# SCH_Mach_nguyen_ly_thiet_ke.net
KiCad netlist of a schematic drawn in Altium Designer
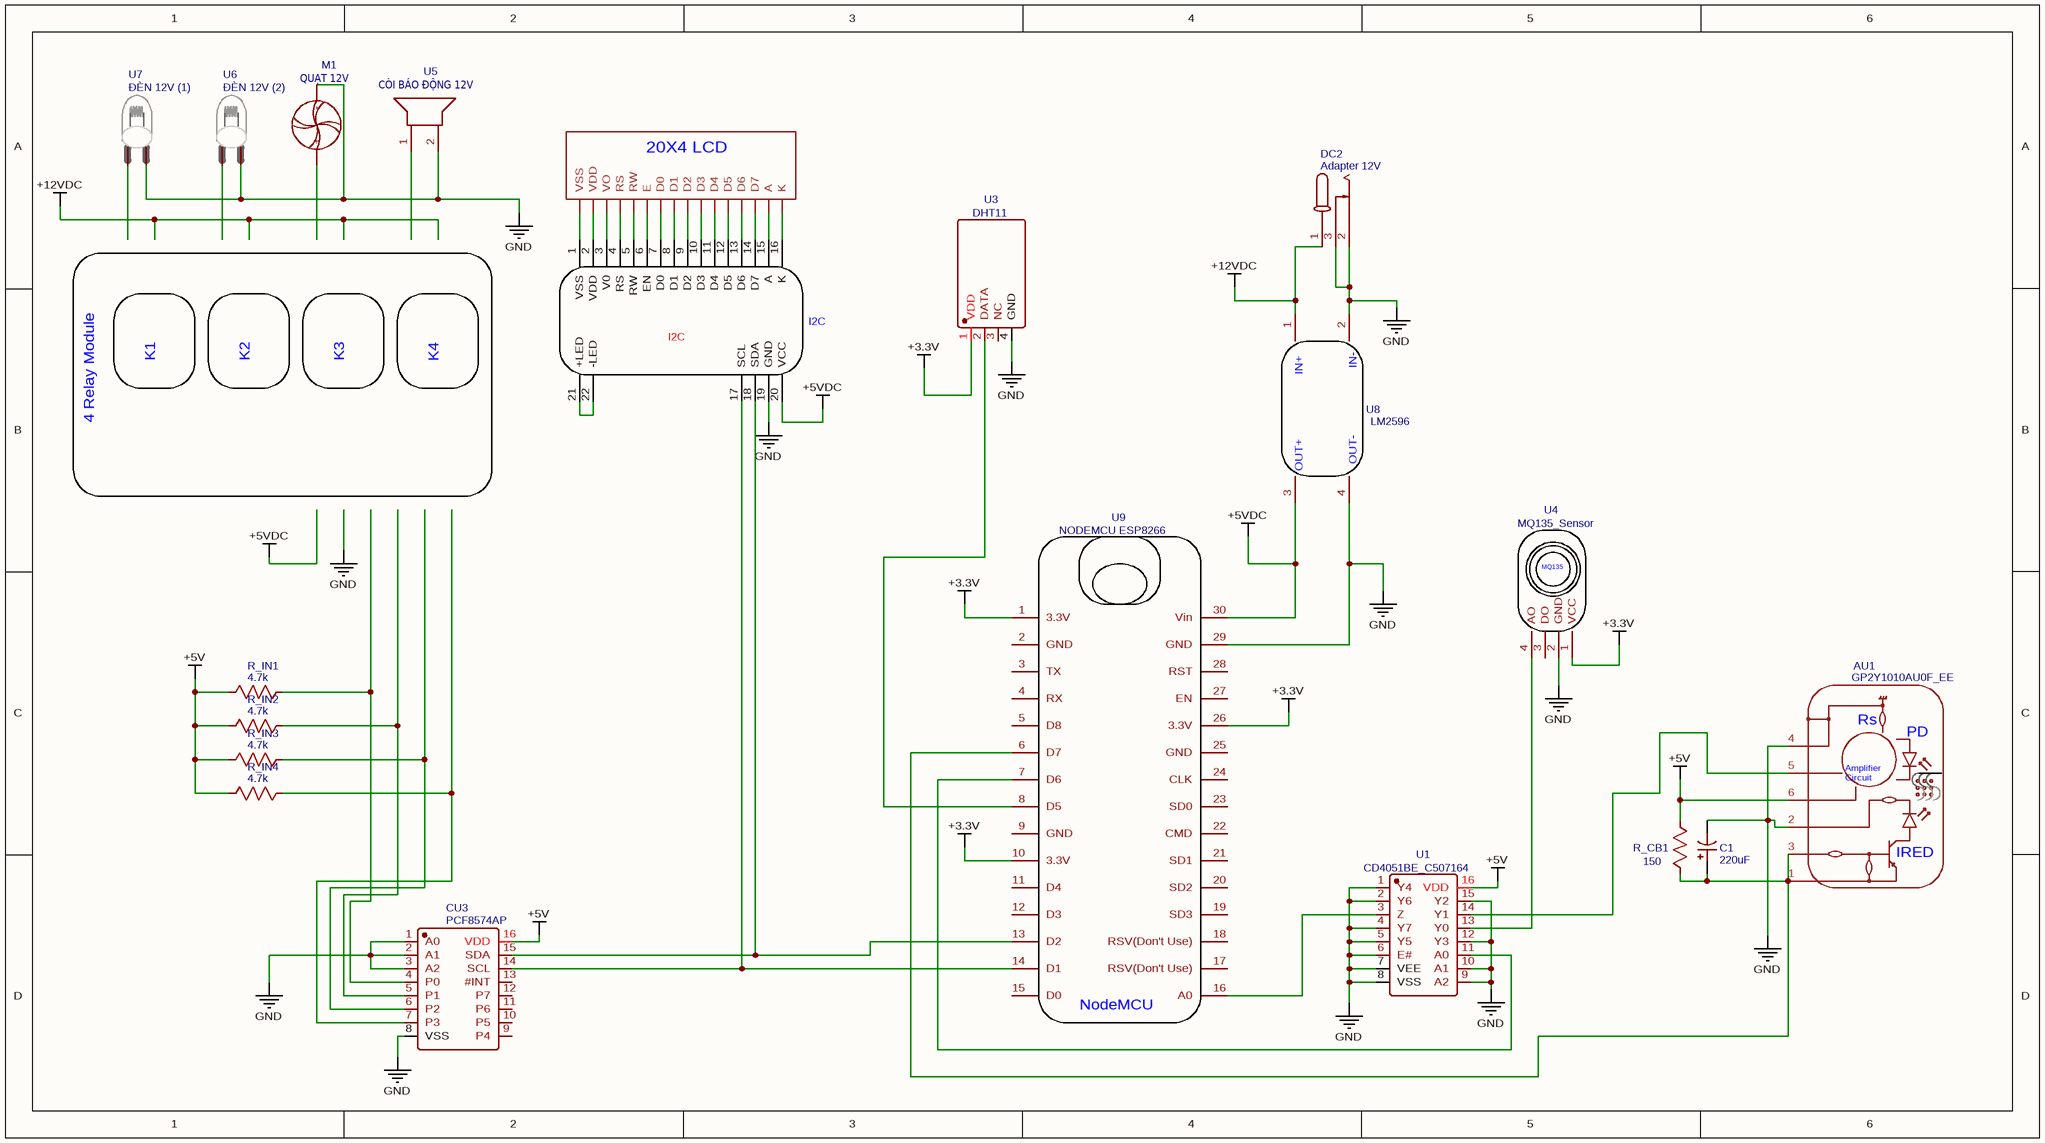
[diagram p0: SCH_Mach_nguyen_ly_thiet_ke.schdoc]

(export (version "E")
  (design (tool "Eeschema 10.0.6"))
  (components
    (comp (ref "AU1")
      (value "GP2Y1010AU0F_EE")
      (footprint "GP2Y1010AU0F")
      (fields (field (name "CONTRIBUTOR") "Ahmed Maher"))
      (libsource (lib "altium-import") (part "root_2_GP2Y1010AU0F_EE_"))
    )
    (comp (ref "C1")
      (value "220uF")
      (footprint "CAP-TH_BD10.0-P5.00-D0.6-FD")
      (fields
        (field (name "MANUFACTURER") "ELNA(伊娜)")
        (field (name "MANUFACTURER PART") "RFO-35V221MH3P#")
        (field (name "CONTRIBUTOR") "lcsc")
      )
      (libsource (lib "altium-import") (part "root_1_220uF_"))
    )
    (comp (ref "CU3")
      (value "PCF8574AP")
      (footprint "DIP-16_L19.2-W6.6-P2.54-LS7.6-BL")
      (fields (field (name "MANUFACTURER") "HGSEMI") (field (name "CONTRIBUTOR") "LCSC"))
      (libsource (lib "altium-import") (part "root_0_PCF8574AP_"))
    )
    (comp (ref "DC2")
      (value "Adapter 12V")
      (footprint "DC-IN-TH_DC005")
      (fields (field (name "MANUFACTURER") "SOFNG") (field (name "MANUFACTURER PART") "DC005-2.0MM"))
      (libsource (lib "altium-import") (part "root_3_Adapter 12V_"))
    )
    (comp (ref "I2C")
      (value "PCF8574AT I2C LCD1602 DRIVER")
      (footprint "PCF8574AT I2C LCD1602 DRIVER 2")
      (fields (field (name "CONTRIBUTOR") "瀬戸口和広"))
      (libsource (lib "altium-import") (part "root_1_PCF8574AT I2C LCD1602 DRIVER_"))
    )
    (comp (ref "M1")
      (value "QUẠT 12V")
      (fields (field (name "CONTRIBUTOR") "KiCAD"))
      (libsource (lib "altium-import") (part "root_2_QUẠT 12V_"))
    )
    (comp (ref "R_CB1")
      (value "150")
      (footprint "R_AXIAL-0.5")
      (fields (field (name "CONTRIBUTOR") "LCEDA_Lib"))
      (libsource (lib "altium-import") (part "root_1_150_"))
    )
    (comp (ref "R_IN1")
      (value "4.7k")
      (footprint "R_AXIAL-0.5")
      (fields (field (name "CONTRIBUTOR") "LCEDA_Lib"))
      (libsource (lib "altium-import") (part "root_0_4.7k_"))
    )
    (comp (ref "R_IN2")
      (value "4.7k")
      (footprint "R_AXIAL-0.5")
      (fields (field (name "CONTRIBUTOR") "LCEDA_Lib"))
      (libsource (lib "altium-import") (part "root_0_4.7k_"))
    )
    (comp (ref "R_IN3")
      (value "4.7k")
      (footprint "R_AXIAL-0.5")
      (fields (field (name "CONTRIBUTOR") "LCEDA_Lib"))
      (libsource (lib "altium-import") (part "root_0_4.7k_"))
    )
    (comp (ref "R_IN4")
      (value "4.7k")
      (footprint "R_AXIAL-0.5")
      (fields (field (name "CONTRIBUTOR") "LCEDA_Lib"))
      (libsource (lib "altium-import") (part "root_0_4.7k_"))
    )
    (comp (ref "TUNNU2")
      (value "LCD-16X28X2-KIT")
      (footprint "LCD-8X2-KIT")
      (fields (field (name "CONTRIBUTOR") "SparkFun"))
      (libsource (lib "altium-import") (part "root_3_LCD-16X28X2-KIT_"))
    )
    (comp (ref "U1")
      (value "CD4051BE_C507164")
      (footprint "DIP-16_L20.0-W6.4-P2.54-LS7.6-BL")
      (fields
        (field (name "MANUFACTURER") "HGSEMI(华冠)")
        (field (name "MANUFACTURER PART") "CD4051BE")
        (field (name "CONTRIBUTOR") "LCSC")
      )
      (libsource (lib "altium-import") (part "root_0_CD4051BE_C507164_"))
    )
    (comp (ref "U3")
      (value "DHT11")
      (footprint "SENSOR-TH_DHT11")
      (fields (field (name "MANUFACTURER") "广州奥松") (field (name "CONTRIBUTOR") "LCSC"))
      (libsource (lib "altium-import") (part "root_1_DHT11_"))
    )
    (comp (ref "U4")
      (value "MQ135_Sensor")
      (footprint "MQ135_MODULO")
      (fields (field (name "CONTRIBUTOR") "rusiru5707"))
      (libsource (lib "altium-import") (part "root_0_MQ135_Sensor_"))
    )
    (comp (ref "U5")
      (value "CÒI BÁO ĐỘNG 12V")
      (footprint "BUZ-TH_BD22.0-P10.00_BUZZER_PIEZO_HX-2212")
      (fields (field (name "MANUFACTURER PART") "HX-2212") (field (name "CONTRIBUTOR") "lcsc"))
      (libsource (lib "altium-import") (part "root_1_CÒI BÁO ĐỘNG 12V_"))
    )
    (comp (ref "U6")
      (value "ĐÈN 12V (2)")
      (footprint "UNIVIBE LAMP-LDR ARRANGEMENT_LAMP")
      (fields (field (name "CONTRIBUTOR") "Erik Holm Nielsen"))
      (libsource (lib "altium-import") (part "root_0_ĐÈN 12V (2)_"))
    )
    (comp (ref "U7")
      (value "ĐÈN 12V (1)")
      (footprint "UNIVIBE LAMP-LDR ARRANGEMENT_LAMP")
      (fields (field (name "CONTRIBUTOR") "Erik Holm Nielsen"))
      (libsource (lib "altium-import") (part "root_0_ĐÈN 12V (1)_"))
    )
    (comp (ref "U8")
      (value "LM2596")
      (footprint "LM2596DC_DC")
      (fields (field (name "CONTRIBUTOR") "utk.pekerjaan"))
      (libsource (lib "altium-import") (part "root_1_LM2596_"))
    )
    (comp (ref "U9")
      (value "NODEMCU ESP8266")
      (footprint "ESP12E_DEVKIT-V1")
      (fields (field (name "CONTRIBUTOR") "Milinda Bandara"))
      (libsource (lib "altium-import") (part "root_0_NODEMCU ESP8266_"))
    )
  )
  (nets
    (net (code "1") (name "+3.3V") (class "Default")
      (node (ref "U3") (pin "1") (pinfunction "VDD_1") (pintype "passive"))
      (node (ref "U4") (pin "1") (pinfunction "VCC_1") (pintype "passive"))
      (node (ref "U9") (pin "1") (pinfunction "3.3V_1") (pintype "passive"))
      (node (ref "U9") (pin "10") (pinfunction "3.3V_10") (pintype "passive"))
      (node (ref "U9") (pin "26") (pinfunction "3.3V_26") (pintype "passive"))
    )
    (net (code "2") (name "+5V") (class "Default")
      (node (ref "AU1") (pin "6") (pinfunction "VCC_6") (pintype "passive"))
      (node (ref "CU3") (pin "16") (pinfunction "VDD_16") (pintype "passive"))
      (node (ref "R_CB1") (pin "2") (pinfunction "2_2") (pintype "passive"))
      (node (ref "R_IN1") (pin "1") (pinfunction "1_1") (pintype "passive"))
      (node (ref "R_IN2") (pin "1") (pinfunction "1_1") (pintype "passive"))
      (node (ref "R_IN3") (pin "1") (pinfunction "1_1") (pintype "passive"))
      (node (ref "R_IN4") (pin "1") (pinfunction "1_1") (pintype "passive"))
      (node (ref "U1") (pin "16") (pinfunction "VDD_16") (pintype "passive"))
    )
    (net (code "3") (name "+5VDC") (class "Default")
      (node (ref "I2C") (pin "20") (pinfunction "VCC_20") (pintype "passive"))
      (node (ref "U8") (pin "3") (pinfunction "3_3") (pintype "passive"))
      (node (ref "U9") (pin "30") (pinfunction "Vin_30") (pintype "passive"))
    )
    (net (code "4") (name "+12VDC") (class "Default")
      (node (ref "DC2") (pin "1") (pinfunction "1_1") (pintype "passive"))
      (node (ref "U8") (pin "1") (pinfunction "1_1") (pintype "passive"))
    )
    (net (code "5") (name "GND") (class "Default")
      (node (ref "AU1") (pin "2") (pinfunction "LEDGND_2") (pintype "passive"))
      (node (ref "AU1") (pin "4") (pinfunction "SGND_4") (pintype "passive"))
      (node (ref "C1") (pin "2") (pinfunction "2_2") (pintype "passive"))
      (node (ref "CU3") (pin "1") (pinfunction "A0_1") (pintype "passive"))
      (node (ref "CU3") (pin "2") (pinfunction "A1_2") (pintype "passive"))
      (node (ref "CU3") (pin "3") (pinfunction "A2_3") (pintype "passive"))
      (node (ref "CU3") (pin "8") (pinfunction "VSS_8") (pintype "passive"))
      (node (ref "DC2") (pin "2") (pinfunction "2_2") (pintype "passive"))
      (node (ref "DC2") (pin "3") (pinfunction "3_3") (pintype "passive"))
      (node (ref "I2C") (pin "19") (pinfunction "GND_19") (pintype "passive"))
      (node (ref "M1") (pin "2") (pinfunction "-_2") (pintype "passive"))
      (node (ref "U1") (pin "1") (pinfunction "Y4_1") (pintype "passive"))
      (node (ref "U1") (pin "10") (pinfunction "A1_10") (pintype "passive"))
      (node (ref "U1") (pin "12") (pinfunction "Y3_12") (pintype "passive"))
      (node (ref "U1") (pin "15") (pinfunction "Y2_15") (pintype "passive"))
      (node (ref "U1") (pin "2") (pinfunction "Y6_2") (pintype "passive"))
      (node (ref "U1") (pin "4") (pinfunction "Y7_4") (pintype "passive"))
      (node (ref "U1") (pin "5") (pinfunction "Y5_5") (pintype "passive"))
      (node (ref "U1") (pin "6") (pinfunction "E#_6") (pintype "passive"))
      (node (ref "U1") (pin "7") (pinfunction "VEE_7") (pintype "passive"))
      (node (ref "U1") (pin "8") (pinfunction "VSS_8") (pintype "passive"))
      (node (ref "U1") (pin "9") (pinfunction "A2_9") (pintype "passive"))
      (node (ref "U3") (pin "4") (pinfunction "GND_4") (pintype "passive"))
      (node (ref "U4") (pin "2") (pinfunction "GND_2") (pintype "passive"))
      (node (ref "U5") (pin "2") (pinfunction "2_2") (pintype "passive"))
      (node (ref "U6") (pin "2") (pinfunction "2_2") (pintype "passive"))
      (node (ref "U7") (pin "2") (pinfunction "2_2") (pintype "passive"))
      (node (ref "U8") (pin "2") (pinfunction "2_2") (pintype "passive"))
      (node (ref "U8") (pin "4") (pinfunction "4_4") (pintype "passive"))
      (node (ref "U9") (pin "29") (pinfunction "GND_29") (pintype "passive"))
    )
    (net (code "6") (name "Net-(AU1-LED)") (class "Default")
      (node (ref "AU1") (pin "1") (pinfunction "VLED_1") (pintype "passive"))
      (node (ref "AU1") (pin "3") (pinfunction "LED_3") (pintype "passive"))
      (node (ref "C1") (pin "1") (pinfunction "1_1") (pintype "passive"))
      (node (ref "R_CB1") (pin "1") (pinfunction "1_1") (pintype "passive"))
      (node (ref "U9") (pin "6") (pinfunction "D7_6") (pintype "passive"))
    )
    (net (code "7") (name "Net-(AU1-VO)") (class "Default")
      (node (ref "AU1") (pin "5") (pinfunction "VO_5") (pintype "passive"))
      (node (ref "U1") (pin "14") (pinfunction "Y1_14") (pintype "passive"))
    )
    (net (code "8") (name "Net-(CU3-P0)") (class "Default")
      (node (ref "CU3") (pin "4") (pinfunction "P0_4") (pintype "passive"))
      (node (ref "R_IN1") (pin "2") (pinfunction "2_2") (pintype "passive"))
    )
    (net (code "9") (name "Net-(CU3-P1)") (class "Default")
      (node (ref "CU3") (pin "5") (pinfunction "P1_5") (pintype "passive"))
      (node (ref "R_IN2") (pin "2") (pinfunction "2_2") (pintype "passive"))
    )
    (net (code "10") (name "Net-(CU3-P2)") (class "Default")
      (node (ref "CU3") (pin "6") (pinfunction "P2_6") (pintype "passive"))
      (node (ref "R_IN3") (pin "2") (pinfunction "2_2") (pintype "passive"))
    )
    (net (code "11") (name "Net-(CU3-P3)") (class "Default")
      (node (ref "CU3") (pin "7") (pinfunction "P3_7") (pintype "passive"))
      (node (ref "R_IN4") (pin "2") (pinfunction "2_2") (pintype "passive"))
    )
    (net (code "12") (name "Net-(CU3-SCL)") (class "Default")
      (node (ref "CU3") (pin "14") (pinfunction "SCL_14") (pintype "passive"))
      (node (ref "I2C") (pin "17") (pinfunction "SCL_17") (pintype "passive"))
      (node (ref "U9") (pin "14") (pinfunction "D1_14") (pintype "passive"))
    )
    (net (code "13") (name "Net-(CU3-SDA)") (class "Default")
      (node (ref "CU3") (pin "15") (pinfunction "SDA_15") (pintype "passive"))
      (node (ref "I2C") (pin "18") (pinfunction "SDA_18") (pintype "passive"))
      (node (ref "U9") (pin "13") (pinfunction "D2_13") (pintype "passive"))
    )
    (net (code "14") (name "Net-(I2C-+LED)") (class "Default")
      (node (ref "I2C") (pin "21") (pinfunction "+LED_21") (pintype "passive"))
      (node (ref "I2C") (pin "22") (pinfunction "-LED_22") (pintype "passive"))
    )
    (net (code "15") (name "Net-(I2C-A)") (class "Default")
      (node (ref "I2C") (pin "15") (pinfunction "A_15") (pintype "passive"))
      (node (ref "TUNNU2") (pin "15") (pinfunction "A_15") (pintype "passive"))
    )
    (net (code "16") (name "Net-(I2C-D0)") (class "Default")
      (node (ref "I2C") (pin "7") (pinfunction "D0_7") (pintype "passive"))
      (node (ref "TUNNU2") (pin "7") (pinfunction "D0_7") (pintype "passive"))
    )
    (net (code "17") (name "Net-(I2C-D1)") (class "Default")
      (node (ref "I2C") (pin "8") (pinfunction "D1_8") (pintype "passive"))
      (node (ref "TUNNU2") (pin "8") (pinfunction "D1_8") (pintype "passive"))
    )
    (net (code "18") (name "Net-(I2C-D2)") (class "Default")
      (node (ref "I2C") (pin "9") (pinfunction "D2_9") (pintype "passive"))
      (node (ref "TUNNU2") (pin "9") (pinfunction "D2_9") (pintype "passive"))
    )
    (net (code "19") (name "Net-(I2C-D3)") (class "Default")
      (node (ref "I2C") (pin "10") (pinfunction "D3_10") (pintype "passive"))
      (node (ref "TUNNU2") (pin "10") (pinfunction "D3_10") (pintype "passive"))
    )
    (net (code "20") (name "Net-(I2C-D4)") (class "Default")
      (node (ref "I2C") (pin "11") (pinfunction "D4_11") (pintype "passive"))
      (node (ref "TUNNU2") (pin "11") (pinfunction "D4_11") (pintype "passive"))
    )
    (net (code "21") (name "Net-(I2C-D5)") (class "Default")
      (node (ref "I2C") (pin "12") (pinfunction "D5_12") (pintype "passive"))
      (node (ref "TUNNU2") (pin "12") (pinfunction "D5_12") (pintype "passive"))
    )
    (net (code "22") (name "Net-(I2C-D6)") (class "Default")
      (node (ref "I2C") (pin "13") (pinfunction "D6_13") (pintype "passive"))
      (node (ref "TUNNU2") (pin "13") (pinfunction "D6_13") (pintype "passive"))
    )
    (net (code "23") (name "Net-(I2C-D7)") (class "Default")
      (node (ref "I2C") (pin "14") (pinfunction "D7_14") (pintype "passive"))
      (node (ref "TUNNU2") (pin "14") (pinfunction "D7_14") (pintype "passive"))
    )
    (net (code "24") (name "Net-(I2C-EN)") (class "Default")
      (node (ref "I2C") (pin "6") (pinfunction "EN_6") (pintype "passive"))
      (node (ref "TUNNU2") (pin "6") (pinfunction "E_6") (pintype "passive"))
    )
    (net (code "25") (name "Net-(I2C-K)") (class "Default")
      (node (ref "I2C") (pin "16") (pinfunction "K_16") (pintype "passive"))
      (node (ref "TUNNU2") (pin "16") (pinfunction "K_16") (pintype "passive"))
    )
    (net (code "26") (name "Net-(I2C-RS)") (class "Default")
      (node (ref "I2C") (pin "4") (pinfunction "RS_4") (pintype "passive"))
      (node (ref "TUNNU2") (pin "4") (pinfunction "RS_4") (pintype "passive"))
    )
    (net (code "27") (name "Net-(I2C-RW)") (class "Default")
      (node (ref "I2C") (pin "5") (pinfunction "RW_5") (pintype "passive"))
      (node (ref "TUNNU2") (pin "5") (pinfunction "RW_5") (pintype "passive"))
    )
    (net (code "28") (name "Net-(I2C-V0)") (class "Default")
      (node (ref "I2C") (pin "3") (pinfunction "V0_3") (pintype "passive"))
      (node (ref "TUNNU2") (pin "3") (pinfunction "VO_3") (pintype "passive"))
    )
    (net (code "29") (name "Net-(I2C-VDD)") (class "Default")
      (node (ref "I2C") (pin "2") (pinfunction "VDD_2") (pintype "passive"))
      (node (ref "TUNNU2") (pin "2") (pinfunction "VDD_2") (pintype "passive"))
    )
    (net (code "30") (name "Net-(I2C-VSS)") (class "Default")
      (node (ref "I2C") (pin "1") (pinfunction "VSS_1") (pintype "passive"))
      (node (ref "TUNNU2") (pin "1") (pinfunction "VSS_1") (pintype "passive"))
    )
    (net (code "31") (name "Net-(U1-A0)") (class "Default")
      (node (ref "U1") (pin "11") (pinfunction "A0_11") (pintype "passive"))
      (node (ref "U9") (pin "7") (pinfunction "D6_7") (pintype "passive"))
    )
    (net (code "32") (name "Net-(U1-Y0)") (class "Default")
      (node (ref "U1") (pin "13") (pinfunction "Y0_13") (pintype "passive"))
      (node (ref "U4") (pin "4") (pinfunction "AO_4") (pintype "passive"))
    )
    (net (code "33") (name "Net-(U1-Z)") (class "Default")
      (node (ref "U1") (pin "3") (pinfunction "Z_3") (pintype "passive"))
      (node (ref "U9") (pin "16") (pinfunction "A0_16") (pintype "passive"))
    )
    (net (code "34") (name "Net-(U3-DATA)") (class "Default")
      (node (ref "U3") (pin "2") (pinfunction "DATA_2") (pintype "passive"))
      (node (ref "U9") (pin "8") (pinfunction "D5_8") (pintype "passive"))
    )
    (net (code "35") (name "unconnected-(CU3-#INT-Pad13)") (class "Default")
      (node (ref "CU3") (pin "13") (pinfunction "#INT_13") (pintype "passive"))
    )
    (net (code "36") (name "unconnected-(CU3-P4-Pad9)") (class "Default")
      (node (ref "CU3") (pin "9") (pinfunction "P4_9") (pintype "passive"))
    )
    (net (code "37") (name "unconnected-(CU3-P5-Pad10)") (class "Default")
      (node (ref "CU3") (pin "10") (pinfunction "P5_10") (pintype "passive"))
    )
    (net (code "38") (name "unconnected-(CU3-P6-Pad11)") (class "Default")
      (node (ref "CU3") (pin "11") (pinfunction "P6_11") (pintype "passive"))
    )
    (net (code "39") (name "unconnected-(CU3-P7-Pad12)") (class "Default")
      (node (ref "CU3") (pin "12") (pinfunction "P7_12") (pintype "passive"))
    )
    (net (code "40") (name "unconnected-(M1-+-Pad1)") (class "Default")
      (node (ref "M1") (pin "1") (pinfunction "+_1") (pintype "passive"))
    )
    (net (code "41") (name "unconnected-(U3-NC-Pad3)") (class "Default")
      (node (ref "U3") (pin "3") (pinfunction "NC_3") (pintype "passive"))
    )
    (net (code "42") (name "unconnected-(U4-DO-Pad3)") (class "Default")
      (node (ref "U4") (pin "3") (pinfunction "DO_3") (pintype "passive"))
    )
    (net (code "43") (name "unconnected-(U5-Pad1)") (class "Default")
      (node (ref "U5") (pin "1") (pinfunction "1_1") (pintype "passive"))
    )
    (net (code "44") (name "unconnected-(U6-Pad1)") (class "Default")
      (node (ref "U6") (pin "1") (pinfunction "1_1") (pintype "passive"))
    )
    (net (code "45") (name "unconnected-(U7-Pad1)") (class "Default")
      (node (ref "U7") (pin "1") (pinfunction "1_1") (pintype "passive"))
    )
    (net (code "46") (name "unconnected-(U9-CLK-Pad24)") (class "Default")
      (node (ref "U9") (pin "24") (pinfunction "CLK_24") (pintype "passive"))
    )
    (net (code "47") (name "unconnected-(U9-CMD-Pad22)") (class "Default")
      (node (ref "U9") (pin "22") (pinfunction "CMD_22") (pintype "passive"))
    )
    (net (code "48") (name "unconnected-(U9-D0-Pad15)") (class "Default")
      (node (ref "U9") (pin "15") (pinfunction "D0_15") (pintype "passive"))
    )
    (net (code "49") (name "unconnected-(U9-D3-Pad12)") (class "Default")
      (node (ref "U9") (pin "12") (pinfunction "D3_12") (pintype "passive"))
    )
    (net (code "50") (name "unconnected-(U9-D4-Pad11)") (class "Default")
      (node (ref "U9") (pin "11") (pinfunction "D4_11") (pintype "passive"))
    )
    (net (code "51") (name "unconnected-(U9-D8-Pad5)") (class "Default")
      (node (ref "U9") (pin "5") (pinfunction "D8_5") (pintype "passive"))
    )
    (net (code "52") (name "unconnected-(U9-EN-Pad27)") (class "Default")
      (node (ref "U9") (pin "27") (pinfunction "EN_27") (pintype "passive"))
    )
    (net (code "53") (name "unconnected-(U9-GND-Pad2)") (class "Default")
      (node (ref "U9") (pin "2") (pinfunction "GND_2") (pintype "passive"))
    )
    (net (code "54") (name "unconnected-(U9-GND-Pad9)") (class "Default")
      (node (ref "U9") (pin "9") (pinfunction "GND_9") (pintype "passive"))
    )
    (net (code "55") (name "unconnected-(U9-GND-Pad25)") (class "Default")
      (node (ref "U9") (pin "25") (pinfunction "GND_25") (pintype "passive"))
    )
    (net (code "56") (name "unconnected-(U9-RST-Pad28)") (class "Default")
      (node (ref "U9") (pin "28") (pinfunction "RST_28") (pintype "passive"))
    )
    (net (code "57") (name "unconnected-(U9-RSV(Don't_Use)-Pad17)") (class "Default")
      (node (ref "U9") (pin "17") (pinfunction "RSV(Don't_Use)_17") (pintype "passive"))
    )
    (net (code "58") (name "unconnected-(U9-RSV(Don't_Use)-Pad18)") (class "Default")
      (node (ref "U9") (pin "18") (pinfunction "RSV(Don't_Use)_18") (pintype "passive"))
    )
    (net (code "59") (name "unconnected-(U9-RX-Pad4)") (class "Default")
      (node (ref "U9") (pin "4") (pinfunction "RX_4") (pintype "passive"))
    )
    (net (code "60") (name "unconnected-(U9-SD0-Pad23)") (class "Default")
      (node (ref "U9") (pin "23") (pinfunction "SD0_23") (pintype "passive"))
    )
    (net (code "61") (name "unconnected-(U9-SD1-Pad21)") (class "Default")
      (node (ref "U9") (pin "21") (pinfunction "SD1_21") (pintype "passive"))
    )
    (net (code "62") (name "unconnected-(U9-SD2-Pad20)") (class "Default")
      (node (ref "U9") (pin "20") (pinfunction "SD2_20") (pintype "passive"))
    )
    (net (code "63") (name "unconnected-(U9-SD3-Pad19)") (class "Default")
      (node (ref "U9") (pin "19") (pinfunction "SD3_19") (pintype "passive"))
    )
    (net (code "64") (name "unconnected-(U9-TX-Pad3)") (class "Default")
      (node (ref "U9") (pin "3") (pinfunction "TX_3") (pintype "passive"))
    )
  )
)
